# Schematic_SensorTapeMaster_v1.net
KiCad netlist of a schematic drawn in Altium Designer
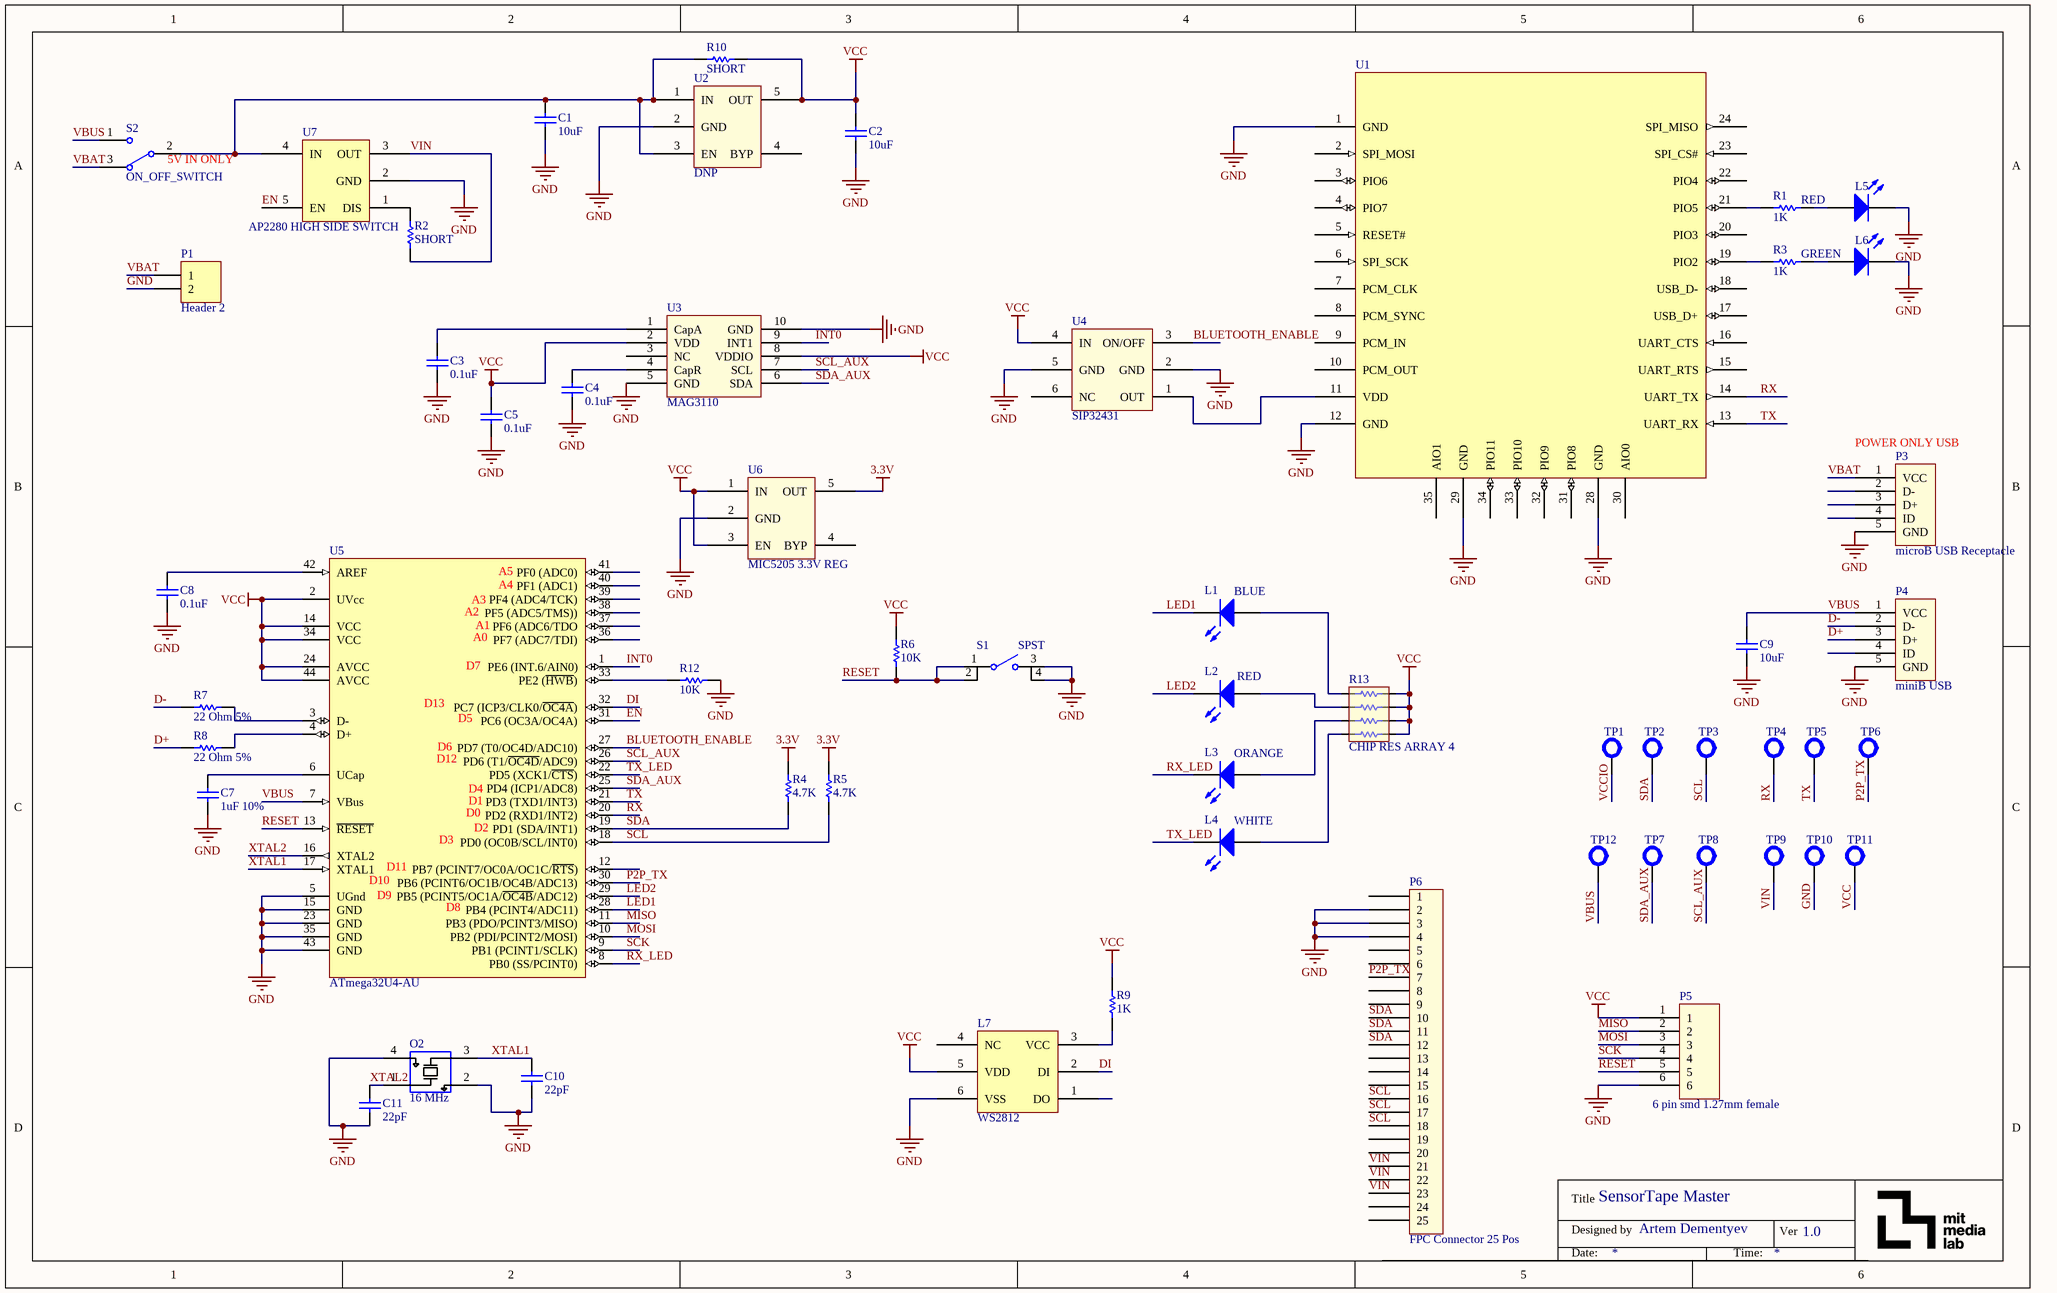
[diagram p0: Schematic_SensorTapeMaster_v1.SchDoc]

(export (version "E")
  (design (tool "Eeschema 10.0.6"))
  (components
    (comp (ref "C1")
      (value "10uF")
      (footprint "0603W")
      (description "SMD Cap 1206")
      (libsource (lib "Artem_Library") (part "Capacitor"))
    )
    (comp (ref "C2")
      (value "10uF")
      (footprint "0603W")
      (description "SMD Cap 1206")
      (libsource (lib "Artem_Library") (part "Capacitor"))
    )
    (comp (ref "C3")
      (value "0.1uF")
      (footprint "0603W")
      (description "SMD Cap 1206")
      (libsource (lib "Artem_Library") (part "Capacitor"))
    )
    (comp (ref "C4")
      (value "0.1uF")
      (footprint "0603W")
      (description "SMD Cap 1206")
      (libsource (lib "Artem_Library") (part "Capacitor"))
    )
    (comp (ref "C5")
      (value "0.1uF")
      (footprint "0603W")
      (description "SMD Cap 1206")
      (libsource (lib "Artem_Library") (part "Capacitor"))
    )
    (comp (ref "C7")
      (value "1uF 10%")
      (footprint "0603W")
      (description "SMD Cap 1206")
      (libsource (lib "Artem_Library") (part "Capacitor"))
    )
    (comp (ref "C8")
      (value "0.1uF")
      (footprint "0603W")
      (description "SMD Cap 1206")
      (libsource (lib "Artem_Library") (part "Capacitor"))
    )
    (comp (ref "C9")
      (value "10uF")
      (footprint "0603W")
      (description "SMD Cap 1206")
      (libsource (lib "Artem_Library") (part "Capacitor"))
    )
    (comp (ref "C10")
      (value "22pF")
      (footprint "0603W")
      (description "SMD Cap 1206")
      (libsource (lib "Artem_Library") (part "Capacitor"))
    )
    (comp (ref "C11")
      (value "22pF")
      (footprint "0603W")
      (description "SMD Cap 1206")
      (libsource (lib "Artem_Library") (part "Capacitor"))
    )
    (comp (ref "L1")
      (value "BLUE")
      (footprint "0603W")
      (description "LED SMD 1206/0603")
      (libsource (lib "Artem_Library") (part "LED"))
    )
    (comp (ref "L2")
      (value "RED")
      (footprint "0603W")
      (description "LED SMD 1206/0603")
      (libsource (lib "Artem_Library") (part "LED"))
    )
    (comp (ref "L3")
      (value "ORANGE")
      (footprint "0603W")
      (description "LED SMD 1206/0603")
      (libsource (lib "Artem_Library") (part "LED"))
    )
    (comp (ref "L4")
      (value "WHITE")
      (footprint "0603W")
      (description "LED SMD 1206/0603")
      (libsource (lib "Artem_Library") (part "LED"))
    )
    (comp (ref "L5")
      (value "LED")
      (footprint "0603W")
      (description "LED SMD 1206/0603")
      (fields (field (name "DIGIKEY PART NUMBER") "160-1447-1-ND"))
      (libsource (lib "Artem_Library") (part "LED"))
    )
    (comp (ref "L6")
      (value "LED")
      (footprint "0603W")
      (description "LED SMD 1206/0603")
      (fields (field (name "DIGIKEY PART NUMBER") "160-1446-1-ND"))
      (libsource (lib "Artem_Library") (part "LED"))
    )
    (comp (ref "L7") (value "WS2812") (footprint "WS2812") (libsource (lib "Artem_Library") (part "WS2812")))
    (comp (ref "O2")
      (value "16 MHz")
      (footprint "CRYSTAL_SMD")
      (description "Surface mount crystal")
      (libsource (lib "Artem_Library") (part "Crystal_SMD"))
    )
    (comp (ref "P1")
      (value "Header 2")
      (footprint "HDR1X2")
      (description "Header, 2-Pin")
      (fields (field (name "PUBLISHER") "Altium Limited"))
      (libsource (lib "Miscellaneous Connectors") (part "Header 2"))
    )
    (comp (ref "P3")
      (value "microB USB Receptacle")
      (footprint "MicroB USB Standarad SMT")
      (fields (field (name "MANUFACTURER") "ZX62-B-5PA(11)"))
      (libsource (lib "Artem_Library") (part "microB USB Receptacle"))
    )
    (comp (ref "P4")
      (value "miniB USB")
      (footprint "UX60SC-MB-5ST")
      (libsource (lib "Artem_Library") (part "miniB USB"))
    )
    (comp (ref "P5")
      (value "6 pin smd 1.27mm female")
      (footprint "6pos 1.27mm")
      (libsource (lib "Artem_Library") (part "6 pin smd 1.27mm female"))
    )
    (comp (ref "P6")
      (value "FPC Connector 25 Pos")
      (footprint "FPC 25 POS")
      (fields (field (name "DIGIKEY PART NUMBER") "A101410CT-ND"))
      (libsource (lib "Artem_Library") (part "FPC Connector 25 Pos"))
    )
    (comp (ref "R1") (value "1K") (footprint "0603W") (libsource (lib "Artem_Library") (part "Resistor")))
    (comp (ref "R2") (value "SHORT") (footprint "0603W") (libsource (lib "Artem_Library") (part "Resistor")))
    (comp (ref "R3") (value "1K") (footprint "0603W") (libsource (lib "Artem_Library") (part "Resistor")))
    (comp (ref "R4") (value "4.7K") (footprint "0603W") (libsource (lib "Artem_Library") (part "Resistor")))
    (comp (ref "R5") (value "4.7K") (footprint "0603W") (libsource (lib "Artem_Library") (part "Resistor")))
    (comp (ref "R6") (value "10K") (footprint "0603W") (libsource (lib "Artem_Library") (part "Resistor")))
    (comp (ref "R7")
      (value "22 Ohm 5%")
      (footprint "0603W")
      (libsource (lib "Artem_Library") (part "Resistor"))
    )
    (comp (ref "R8")
      (value "22 Ohm 5%")
      (footprint "0603W")
      (libsource (lib "Artem_Library") (part "Resistor"))
    )
    (comp (ref "R9") (value "1K") (footprint "0603W") (libsource (lib "Artem_Library") (part "Resistor")))
    (comp (ref "R10") (value "SHORT") (footprint "0603W") (libsource (lib "Artem_Library") (part "Resistor")))
    (comp (ref "R12") (value "10K") (footprint "0603W") (libsource (lib "Artem_Library") (part "Resistor")))
    (comp (ref "R13")
      (value "CHIP RES ARRAY 4")
      (footprint "RES ARRAY 4 1206")
      (libsource (lib "Artem_Library") (part "CHIP RES ARRAY 4"))
    )
    (comp (ref "S1")
      (value "SPST")
      (footprint "EVQQ2 Switch")
      (description "THD Button Switch")
      (libsource (lib "Artem_Library") (part "SPST"))
    )
    (comp (ref "S2")
      (value "ON_OFF_SWITCH")
      (footprint "SS321 Switch")
      (description "SPDT SMD Side Switch")
      (libsource (lib "Artem_Library") (part "ON_OFF_SWITCH"))
    )
    (comp (ref "TP1")
      (value "Test point small")
      (footprint "Test point small")
      (libsource (lib "Artem_Library") (part "Test point small"))
    )
    (comp (ref "TP2")
      (value "Test point small")
      (footprint "Test point small")
      (libsource (lib "Artem_Library") (part "Test point small"))
    )
    (comp (ref "TP3")
      (value "Test point small")
      (footprint "Test point small")
      (libsource (lib "Artem_Library") (part "Test point small"))
    )
    (comp (ref "TP4")
      (value "Test point small")
      (footprint "Test point small")
      (libsource (lib "Artem_Library") (part "Test point small"))
    )
    (comp (ref "TP5")
      (value "Test point small")
      (footprint "Test point small")
      (libsource (lib "Artem_Library") (part "Test point small"))
    )
    (comp (ref "TP6")
      (value "Test point small")
      (footprint "Test point small")
      (libsource (lib "Artem_Library") (part "Test point small"))
    )
    (comp (ref "TP7")
      (value "Test point small")
      (footprint "Test point small")
      (libsource (lib "Artem_Library") (part "Test point small"))
    )
    (comp (ref "TP8")
      (value "Test point small")
      (footprint "Test point small")
      (libsource (lib "Artem_Library") (part "Test point small"))
    )
    (comp (ref "TP9")
      (value "Test point small")
      (footprint "Test point small")
      (libsource (lib "Artem_Library") (part "Test point small"))
    )
    (comp (ref "TP10")
      (value "Test point small")
      (footprint "Test point small")
      (libsource (lib "Artem_Library") (part "Test point small"))
    )
    (comp (ref "TP11")
      (value "Test point small")
      (footprint "Test point small")
      (libsource (lib "Artem_Library") (part "Test point small"))
    )
    (comp (ref "TP12")
      (value "Test point small")
      (footprint "Test point small")
      (libsource (lib "Artem_Library") (part "Test point small"))
    )
    (comp (ref "U1")
      (value "~")
      (footprint "RN-42 LAND")
      (description "Bluetooth serial modem")
      (fields (field (name "DIGIKEY PART NUMBER") "740-1038-ND"))
      (libsource (lib "Artem_Library") (part "RN42"))
    )
    (comp (ref "U2")
      (value "DNP")
      (footprint "SOT-23-5")
      (description "5V LDO SMD")
      (libsource (lib "Artem_Library") (part "MIC5205_VOLTAGE_REG"))
    )
    (comp (ref "U3")
      (value "MAG3110")
      (footprint "10-VFDFN")
      (libsource (lib "Artem_Library") (part "MAG3110"))
    )
    (comp (ref "U4")
      (value "SIP32431")
      (footprint "SOT363")
      (description "High side switch")
      (fields (field (name "DIGIKEY PART NUMBER") "SIP32431DR3-T1GE3CT-ND"))
      (libsource (lib "Artem_Library") (part "SIP32431"))
    )
    (comp (ref "U5")
      (value "ATmega32U4-AU")
      (footprint "44ML_N")
      (fields (field (name "PUBLISHER") "Altium Limited"))
      (libsource (lib "Atmel Microcontroller 8-Bit megaAVR") (part "ATmega32U4-AU"))
    )
    (comp (ref "U6")
      (value "MIC5205 3.3V REG")
      (footprint "SOT-23-5")
      (description "5V LDO SMD")
      (libsource (lib "Artem_Library") (part "MIC5205_VOLTAGE_REG"))
    )
    (comp (ref "U7")
      (value "AP2280 HIGH SIDE SWITCH")
      (footprint "SOT25")
      (description "2A High side switch")
      (libsource (lib "Artem_Library") (part "AP2280 HIGH SIDE SWITCH"))
    )
  )
  (nets
    (net (code "1") (name "/BLUETOOTH_ENABLE") (class "Default")
      (node (ref "U4") (pin "3") (pinfunction "ON/OFF_3") (pintype "passive"))
      (node (ref "U5") (pin "27") (pinfunction "PD7_(T0/OC4D/ADC10)_27") (pintype "bidirectional"))
    )
    (net (code "2") (name "/D+") (class "Default")
      (node (ref "P4") (pin "3") (pinfunction "D+_3") (pintype "passive"))
      (node (ref "R8") (pin "2") (pinfunction "2_2") (pintype "passive"))
    )
    (net (code "3") (name "/D-") (class "Default")
      (node (ref "P4") (pin "2") (pinfunction "D-_2") (pintype "passive"))
      (node (ref "R7") (pin "2") (pinfunction "2_2") (pintype "passive"))
    )
    (net (code "4") (name "/DI") (class "Default")
      (node (ref "L7") (pin "2") (pinfunction "DI_2") (pintype "passive"))
      (node (ref "U5") (pin "32") (pinfunction "PC7_(ICP3/CLK0/~{OC4A})_32") (pintype "bidirectional"))
    )
    (net (code "5") (name "/EN") (class "Default")
      (node (ref "U5") (pin "31") (pinfunction "PC6_(OC3A/OC4A)_31") (pintype "bidirectional"))
      (node (ref "U7") (pin "5") (pinfunction "EN_5") (pintype "passive"))
    )
    (net (code "6") (name "/INT0") (class "Default")
      (node (ref "U3") (pin "9") (pinfunction "INT1_9") (pintype "passive"))
      (node (ref "U5") (pin "1") (pinfunction "PE6_(INT.6/AIN0)_1") (pintype "bidirectional"))
    )
    (net (code "7") (name "/LED1") (class "Default")
      (node (ref "L1") (pin "2") (pinfunction "K_2") (pintype "passive"))
      (node (ref "U5") (pin "28") (pinfunction "PB4_(PCINT4/ADC11)_28") (pintype "bidirectional"))
    )
    (net (code "8") (name "/LED2") (class "Default")
      (node (ref "L2") (pin "2") (pinfunction "K_2") (pintype "passive"))
      (node (ref "U5") (pin "29") (pinfunction "PB5_(PCINT5/OC1A/~{OC4B}/ADC12)_29") (pintype "bidirectional"))
    )
    (net (code "9") (name "/MISO") (class "Default")
      (node (ref "P5") (pin "2") (pinfunction "2_2") (pintype "passive"))
      (node (ref "U5") (pin "11") (pinfunction "PB3_(PDO/PCINT3/MISO)_11") (pintype "bidirectional"))
    )
    (net (code "10") (name "/MOSI") (class "Default")
      (node (ref "P5") (pin "3") (pinfunction "3_3") (pintype "passive"))
      (node (ref "U5") (pin "10") (pinfunction "PB2_(PDI/PCINT2/MOSI)_10") (pintype "bidirectional"))
    )
    (net (code "11") (name "/P2P_TX") (class "Default")
      (node (ref "P6") (pin "7") (pinfunction "7_7") (pintype "passive"))
      (node (ref "TP6") (pin "0") (pinfunction "0_0") (pintype "passive"))
      (node (ref "U5") (pin "30") (pinfunction "PB6_(PCINT6/OC1B/OC4B/ADC13)_30") (pintype "bidirectional"))
    )
    (net (code "12") (name "/RESET") (class "Default")
      (node (ref "P5") (pin "5") (pinfunction "5_5") (pintype "passive"))
      (node (ref "R6") (pin "1") (pinfunction "1_1") (pintype "passive"))
      (node (ref "S1") (pin "1") (pinfunction "COMMON_1") (pintype "passive"))
      (node (ref "S1") (pin "2") (pinfunction "2_2") (pintype "passive"))
      (node (ref "U5") (pin "13") (pinfunction "~{RESET}_13") (pintype "input"))
    )
    (net (code "13") (name "/RX") (class "Default")
      (node (ref "TP4") (pin "0") (pinfunction "0_0") (pintype "passive"))
      (node (ref "U1") (pin "14") (pinfunction "UART_TX_14") (pintype "output"))
      (node (ref "U5") (pin "20") (pinfunction "PD2_(RXD1/INT2)_20") (pintype "bidirectional"))
    )
    (net (code "14") (name "/RX_LED") (class "Default")
      (node (ref "L3") (pin "2") (pinfunction "K_2") (pintype "passive"))
      (node (ref "U5") (pin "8") (pinfunction "PB0_(SS/PCINT0)_8") (pintype "bidirectional"))
    )
    (net (code "15") (name "/SCK") (class "Default")
      (node (ref "P5") (pin "4") (pinfunction "4_4") (pintype "passive"))
      (node (ref "U5") (pin "9") (pinfunction "PB1_(PCINT1/SCLK)_9") (pintype "bidirectional"))
    )
    (net (code "16") (name "/SCL") (class "Default")
      (node (ref "P6") (pin "16") (pinfunction "16_16") (pintype "passive"))
      (node (ref "P6") (pin "17") (pinfunction "17_17") (pintype "passive"))
      (node (ref "P6") (pin "18") (pinfunction "18_18") (pintype "passive"))
      (node (ref "R5") (pin "1") (pinfunction "1_1") (pintype "passive"))
      (node (ref "TP3") (pin "0") (pinfunction "0_0") (pintype "passive"))
      (node (ref "U5") (pin "18") (pinfunction "PD0_(OC0B/SCL/INT0)_18") (pintype "bidirectional"))
    )
    (net (code "17") (name "/SCL_AUX") (class "Default")
      (node (ref "TP8") (pin "0") (pinfunction "0_0") (pintype "passive"))
      (node (ref "U3") (pin "7") (pinfunction "SCL_7") (pintype "passive"))
      (node (ref "U5") (pin "26") (pinfunction "PD6_(T1/~{OC4D}/ADC9)_26") (pintype "bidirectional"))
    )
    (net (code "18") (name "/SDA") (class "Default")
      (node (ref "P6") (pin "10") (pinfunction "10_10") (pintype "passive"))
      (node (ref "P6") (pin "11") (pinfunction "11_11") (pintype "passive"))
      (node (ref "P6") (pin "12") (pinfunction "12_12") (pintype "passive"))
      (node (ref "R4") (pin "2") (pinfunction "2_2") (pintype "passive"))
      (node (ref "TP2") (pin "0") (pinfunction "0_0") (pintype "passive"))
      (node (ref "U5") (pin "19") (pinfunction "PD1_(SDA/INT1)_19") (pintype "bidirectional"))
    )
    (net (code "19") (name "/SDA_AUX") (class "Default")
      (node (ref "TP7") (pin "0") (pinfunction "0_0") (pintype "passive"))
      (node (ref "U3") (pin "6") (pinfunction "SDA_6") (pintype "passive"))
      (node (ref "U5") (pin "25") (pinfunction "PD4_(ICP1/ADC8)_25") (pintype "bidirectional"))
    )
    (net (code "20") (name "/TX") (class "Default")
      (node (ref "TP5") (pin "0") (pinfunction "0_0") (pintype "passive"))
      (node (ref "U1") (pin "13") (pinfunction "UART_RX_13") (pintype "input"))
      (node (ref "U5") (pin "21") (pinfunction "PD3_(TXD1/INT3)_21") (pintype "bidirectional"))
    )
    (net (code "21") (name "/TX_LED") (class "Default")
      (node (ref "L4") (pin "2") (pinfunction "K_2") (pintype "passive"))
      (node (ref "U5") (pin "22") (pinfunction "PD5_(XCK1/~{CTS})_22") (pintype "bidirectional"))
    )
    (net (code "22") (name "/VBAT") (class "Default")
      (node (ref "P1") (pin "1") (pinfunction "1_1") (pintype "passive"))
      (node (ref "P3") (pin "1") (pinfunction "VCC_1") (pintype "passive"))
      (node (ref "S2") (pin "3") (pinfunction "3_3") (pintype "passive"))
    )
    (net (code "23") (name "/VBUS") (class "Default")
      (node (ref "C9") (pin "1") (pinfunction "1_1") (pintype "passive"))
      (node (ref "P4") (pin "1") (pinfunction "VCC_1") (pintype "passive"))
      (node (ref "S2") (pin "1") (pinfunction "1_1") (pintype "passive"))
      (node (ref "TP12") (pin "0") (pinfunction "0_0") (pintype "passive"))
      (node (ref "U5") (pin "7") (pinfunction "VBus_7") (pintype "input"))
    )
    (net (code "24") (name "/VCCIO") (class "Default")
      (node (ref "TP1") (pin "0") (pinfunction "0_0") (pintype "passive"))
    )
    (net (code "25") (name "/VIN") (class "Default")
      (node (ref "P6") (pin "21") (pinfunction "21_21") (pintype "passive"))
      (node (ref "P6") (pin "22") (pinfunction "22_22") (pintype "passive"))
      (node (ref "P6") (pin "23") (pinfunction "23_23") (pintype "passive"))
      (node (ref "R2") (pin "1") (pinfunction "1_1") (pintype "passive"))
      (node (ref "TP9") (pin "0") (pinfunction "0_0") (pintype "passive"))
      (node (ref "U7") (pin "3") (pinfunction "OUT_3") (pintype "passive"))
    )
    (net (code "26") (name "/XTAL1") (class "Default")
      (node (ref "C10") (pin "1") (pinfunction "1_1") (pintype "passive"))
      (node (ref "O2") (pin "3") (pinfunction "XOUT_3") (pintype "passive"))
      (node (ref "U5") (pin "17") (pinfunction "XTAL1_17") (pintype "input"))
    )
    (net (code "27") (name "/XTAL2") (class "Default")
      (node (ref "C11") (pin "1") (pinfunction "1_1") (pintype "passive"))
      (node (ref "O2") (pin "1") (pinfunction "XIN_1") (pintype "passive"))
      (node (ref "U5") (pin "16") (pinfunction "XTAL2_16") (pintype "output"))
    )
    (net (code "28") (name "3.3V") (class "Default")
      (node (ref "R4") (pin "1") (pinfunction "1_1") (pintype "passive"))
      (node (ref "R5") (pin "2") (pinfunction "2_2") (pintype "passive"))
      (node (ref "U6") (pin "5") (pinfunction "OUT_5") (pintype "passive"))
    )
    (net (code "29") (name "GND") (class "Default")
      (node (ref "C1") (pin "1") (pinfunction "1_1") (pintype "passive"))
      (node (ref "C10") (pin "2") (pinfunction "2_2") (pintype "passive"))
      (node (ref "C11") (pin "2") (pinfunction "2_2") (pintype "passive"))
      (node (ref "C2") (pin "1") (pinfunction "1_1") (pintype "passive"))
      (node (ref "C3") (pin "1") (pinfunction "1_1") (pintype "passive"))
      (node (ref "C4") (pin "1") (pinfunction "1_1") (pintype "passive"))
      (node (ref "C5") (pin "1") (pinfunction "1_1") (pintype "passive"))
      (node (ref "C7") (pin "2") (pinfunction "2_2") (pintype "passive"))
      (node (ref "C8") (pin "2") (pinfunction "2_2") (pintype "passive"))
      (node (ref "C9") (pin "2") (pinfunction "2_2") (pintype "passive"))
      (node (ref "L5") (pin "2") (pinfunction "K_2") (pintype "passive"))
      (node (ref "L6") (pin "2") (pinfunction "K_2") (pintype "passive"))
      (node (ref "L7") (pin "6") (pinfunction "VSS_6") (pintype "passive"))
      (node (ref "O2") (pin "2") (pinfunction "Gnd_2") (pintype "passive"))
      (node (ref "O2") (pin "4") (pinfunction "Gnd_4") (pintype "passive"))
      (node (ref "P1") (pin "2") (pinfunction "2_2") (pintype "passive"))
      (node (ref "P3") (pin "5") (pinfunction "GND_5") (pintype "passive"))
      (node (ref "P4") (pin "5") (pinfunction "GND_5") (pintype "passive"))
      (node (ref "P5") (pin "6") (pinfunction "6_6") (pintype "passive"))
      (node (ref "P6") (pin "2") (pinfunction "2_2") (pintype "passive"))
      (node (ref "P6") (pin "3") (pinfunction "3_3") (pintype "passive"))
      (node (ref "P6") (pin "4") (pinfunction "4_4") (pintype "passive"))
      (node (ref "R12") (pin "1") (pinfunction "1_1") (pintype "passive"))
      (node (ref "S1") (pin "3") (pinfunction "3_3") (pintype "passive"))
      (node (ref "S1") (pin "4") (pinfunction "4_4") (pintype "passive"))
      (node (ref "TP10") (pin "0") (pinfunction "0_0") (pintype "passive"))
      (node (ref "U1") (pin "1") (pinfunction "GND_1") (pintype "power_in"))
      (node (ref "U1") (pin "12") (pinfunction "GND_12") (pintype "power_in"))
      (node (ref "U1") (pin "28") (pinfunction "GND_28") (pintype "power_in"))
      (node (ref "U1") (pin "29") (pinfunction "GND_29") (pintype "power_in"))
      (node (ref "U2") (pin "2") (pinfunction "GND_2") (pintype "passive"))
      (node (ref "U3") (pin "10") (pinfunction "GND_10") (pintype "passive"))
      (node (ref "U3") (pin "5") (pinfunction "GND_5") (pintype "passive"))
      (node (ref "U4") (pin "2") (pinfunction "GND_2") (pintype "passive"))
      (node (ref "U4") (pin "5") (pinfunction "GND_5") (pintype "passive"))
      (node (ref "U5") (pin "15") (pinfunction "GND_15") (pintype "power_in"))
      (node (ref "U5") (pin "23") (pinfunction "GND_23") (pintype "power_in"))
      (node (ref "U5") (pin "35") (pinfunction "GND_35") (pintype "power_in"))
      (node (ref "U5") (pin "43") (pinfunction "GND_43") (pintype "power_in"))
      (node (ref "U5") (pin "5") (pinfunction "UGnd_5") (pintype "power_in"))
      (node (ref "U6") (pin "2") (pinfunction "GND_2") (pintype "passive"))
      (node (ref "U7") (pin "2") (pinfunction "GND_2") (pintype "passive"))
    )
    (net (code "30") (name "Net-(L1-A)") (class "Default")
      (node (ref "L1") (pin "1") (pinfunction "A_1") (pintype "passive"))
      (node (ref "R13") (pin "1") (pinfunction "1_1") (pintype "passive"))
    )
    (net (code "31") (name "Net-(L2-A)") (class "Default")
      (node (ref "L2") (pin "1") (pinfunction "A_1") (pintype "passive"))
      (node (ref "R13") (pin "2") (pinfunction "2_2") (pintype "passive"))
    )
    (net (code "32") (name "Net-(L3-A)") (class "Default")
      (node (ref "L3") (pin "1") (pinfunction "A_1") (pintype "passive"))
      (node (ref "R13") (pin "3") (pinfunction "3_3") (pintype "passive"))
    )
    (net (code "33") (name "Net-(L4-A)") (class "Default")
      (node (ref "L4") (pin "1") (pinfunction "A_1") (pintype "passive"))
      (node (ref "R13") (pin "4") (pinfunction "4_4") (pintype "passive"))
    )
    (net (code "34") (name "Net-(L5-A)") (class "Default")
      (node (ref "L5") (pin "1") (pinfunction "A_1") (pintype "passive"))
      (node (ref "R1") (pin "1") (pinfunction "1_1") (pintype "passive"))
    )
    (net (code "35") (name "Net-(L6-A)") (class "Default")
      (node (ref "L6") (pin "1") (pinfunction "A_1") (pintype "passive"))
      (node (ref "R3") (pin "1") (pinfunction "1_1") (pintype "passive"))
    )
    (net (code "36") (name "Net-(L7-VCC)") (class "Default")
      (node (ref "L7") (pin "3") (pinfunction "VCC_3") (pintype "passive"))
      (node (ref "R9") (pin "1") (pinfunction "1_1") (pintype "passive"))
    )
    (net (code "37") (name "Net-(U1-PIO2)") (class "Default")
      (node (ref "R3") (pin "2") (pinfunction "2_2") (pintype "passive"))
      (node (ref "U1") (pin "19") (pinfunction "PIO2_19") (pintype "bidirectional"))
    )
    (net (code "38") (name "Net-(U1-PIO5)") (class "Default")
      (node (ref "R1") (pin "2") (pinfunction "2_2") (pintype "passive"))
      (node (ref "U1") (pin "21") (pinfunction "PIO5_21") (pintype "bidirectional"))
    )
    (net (code "39") (name "Net-(U1-VDD)") (class "Default")
      (node (ref "U1") (pin "11") (pinfunction "VDD_11") (pintype "power_in"))
      (node (ref "U4") (pin "1") (pinfunction "OUT_1") (pintype "passive"))
    )
    (net (code "40") (name "Net-(U2-EN)") (class "Default")
      (node (ref "C1") (pin "2") (pinfunction "2_2") (pintype "passive"))
      (node (ref "R10") (pin "2") (pinfunction "2_2") (pintype "passive"))
      (node (ref "S2") (pin "2") (pinfunction "2_2") (pintype "passive"))
      (node (ref "U2") (pin "1") (pinfunction "IN_1") (pintype "passive"))
      (node (ref "U2") (pin "3") (pinfunction "EN_3") (pintype "passive"))
      (node (ref "U7") (pin "4") (pinfunction "IN_4") (pintype "passive"))
    )
    (net (code "41") (name "Net-(U3-CapA)") (class "Default")
      (node (ref "C3") (pin "2") (pinfunction "2_2") (pintype "passive"))
      (node (ref "U3") (pin "1") (pinfunction "CapA_1") (pintype "passive"))
    )
    (net (code "42") (name "Net-(U3-CapR)") (class "Default")
      (node (ref "C4") (pin "2") (pinfunction "2_2") (pintype "passive"))
      (node (ref "U3") (pin "4") (pinfunction "CapR_4") (pintype "passive"))
    )
    (net (code "43") (name "Net-(U5-AREF)") (class "Default")
      (node (ref "C8") (pin "1") (pinfunction "1_1") (pintype "passive"))
      (node (ref "U5") (pin "42") (pinfunction "AREF_42") (pintype "input"))
    )
    (net (code "44") (name "Net-(U5-D+)") (class "Default")
      (node (ref "R8") (pin "1") (pinfunction "1_1") (pintype "passive"))
      (node (ref "U5") (pin "4") (pinfunction "D+_4") (pintype "bidirectional"))
    )
    (net (code "45") (name "Net-(U5-D-)") (class "Default")
      (node (ref "R7") (pin "1") (pinfunction "1_1") (pintype "passive"))
      (node (ref "U5") (pin "3") (pinfunction "D-_3") (pintype "bidirectional"))
    )
    (net (code "46") (name "Net-(U5-PE2_(~{HWB}))") (class "Default")
      (node (ref "R12") (pin "2") (pinfunction "2_2") (pintype "passive"))
      (node (ref "U5") (pin "33") (pinfunction "PE2_(~{HWB})_33") (pintype "bidirectional"))
    )
    (net (code "47") (name "Net-(U5-UCap)") (class "Default")
      (node (ref "C7") (pin "1") (pinfunction "1_1") (pintype "passive"))
      (node (ref "U5") (pin "6") (pinfunction "UCap_6") (pintype "passive"))
    )
    (net (code "48") (name "Net-(U7-DIS)") (class "Default")
      (node (ref "R2") (pin "2") (pinfunction "2_2") (pintype "passive"))
      (node (ref "U7") (pin "1") (pinfunction "DIS_1") (pintype "passive"))
    )
    (net (code "49") (name "VCC") (class "Default")
      (node (ref "C2") (pin "2") (pinfunction "2_2") (pintype "passive"))
      (node (ref "C5") (pin "2") (pinfunction "2_2") (pintype "passive"))
      (node (ref "L7") (pin "5") (pinfunction "VDD_5") (pintype "passive"))
      (node (ref "P5") (pin "1") (pinfunction "1_1") (pintype "passive"))
      (node (ref "R10") (pin "1") (pinfunction "1_1") (pintype "passive"))
      (node (ref "R13") (pin "5") (pinfunction "5_5") (pintype "passive"))
      (node (ref "R13") (pin "6") (pinfunction "6_6") (pintype "passive"))
      (node (ref "R13") (pin "7") (pinfunction "7_7") (pintype "passive"))
      (node (ref "R13") (pin "8") (pinfunction "8_8") (pintype "passive"))
      (node (ref "R6") (pin "2") (pinfunction "2_2") (pintype "passive"))
      (node (ref "R9") (pin "2") (pinfunction "2_2") (pintype "passive"))
      (node (ref "TP11") (pin "0") (pinfunction "0_0") (pintype "passive"))
      (node (ref "U2") (pin "5") (pinfunction "OUT_5") (pintype "passive"))
      (node (ref "U3") (pin "2") (pinfunction "VDD_2") (pintype "passive"))
      (node (ref "U3") (pin "8") (pinfunction "VDDIO_8") (pintype "passive"))
      (node (ref "U4") (pin "4") (pinfunction "IN_4") (pintype "passive"))
      (node (ref "U5") (pin "14") (pinfunction "VCC_14") (pintype "power_in"))
      (node (ref "U5") (pin "2") (pinfunction "UVcc_2") (pintype "power_in"))
      (node (ref "U5") (pin "24") (pinfunction "AVCC_24") (pintype "power_in"))
      (node (ref "U5") (pin "34") (pinfunction "VCC_34") (pintype "power_in"))
      (node (ref "U5") (pin "44") (pinfunction "AVCC_44") (pintype "power_in"))
      (node (ref "U6") (pin "1") (pinfunction "IN_1") (pintype "passive"))
      (node (ref "U6") (pin "3") (pinfunction "EN_3") (pintype "passive"))
    )
    (net (code "50") (name "unconnected-(L7-DO-Pad1)") (class "Default")
      (node (ref "L7") (pin "1") (pinfunction "DO_1") (pintype "passive"))
    )
    (net (code "51") (name "unconnected-(L7-NC-Pad4)") (class "Default")
      (node (ref "L7") (pin "4") (pinfunction "NC_4") (pintype "passive"))
    )
    (net (code "52") (name "unconnected-(P3-D+-Pad3)") (class "Default")
      (node (ref "P3") (pin "3") (pinfunction "D+_3") (pintype "passive"))
    )
    (net (code "53") (name "unconnected-(P3-D--Pad2)") (class "Default")
      (node (ref "P3") (pin "2") (pinfunction "D-_2") (pintype "passive"))
    )
    (net (code "54") (name "unconnected-(P3-ID-Pad4)") (class "Default")
      (node (ref "P3") (pin "4") (pinfunction "ID_4") (pintype "passive"))
    )
    (net (code "55") (name "unconnected-(P4-ID-Pad4)") (class "Default")
      (node (ref "P4") (pin "4") (pinfunction "ID_4") (pintype "passive"))
    )
    (net (code "56") (name "unconnected-(P6-Pad1)") (class "Default")
      (node (ref "P6") (pin "1") (pinfunction "1_1") (pintype "passive"))
    )
    (net (code "57") (name "unconnected-(P6-Pad5)") (class "Default")
      (node (ref "P6") (pin "5") (pinfunction "5_5") (pintype "passive"))
    )
    (net (code "58") (name "unconnected-(P6-Pad6)") (class "Default")
      (node (ref "P6") (pin "6") (pinfunction "6_6") (pintype "passive"))
    )
    (net (code "59") (name "unconnected-(P6-Pad8)") (class "Default")
      (node (ref "P6") (pin "8") (pinfunction "8_8") (pintype "passive"))
    )
    (net (code "60") (name "unconnected-(P6-Pad9)") (class "Default")
      (node (ref "P6") (pin "9") (pinfunction "9_9") (pintype "passive"))
    )
    (net (code "61") (name "unconnected-(P6-Pad13)") (class "Default")
      (node (ref "P6") (pin "13") (pinfunction "13_13") (pintype "passive"))
    )
    (net (code "62") (name "unconnected-(P6-Pad14)") (class "Default")
      (node (ref "P6") (pin "14") (pinfunction "14_14") (pintype "passive"))
    )
    (net (code "63") (name "unconnected-(P6-Pad15)") (class "Default")
      (node (ref "P6") (pin "15") (pinfunction "15_15") (pintype "passive"))
    )
    (net (code "64") (name "unconnected-(P6-Pad19)") (class "Default")
      (node (ref "P6") (pin "19") (pinfunction "19_19") (pintype "passive"))
    )
    (net (code "65") (name "unconnected-(P6-Pad20)") (class "Default")
      (node (ref "P6") (pin "20") (pinfunction "20_20") (pintype "passive"))
    )
    (net (code "66") (name "unconnected-(P6-Pad24)") (class "Default")
      (node (ref "P6") (pin "24") (pinfunction "24_24") (pintype "passive"))
    )
    (net (code "67") (name "unconnected-(P6-Pad25)") (class "Default")
      (node (ref "P6") (pin "25") (pinfunction "25_25") (pintype "passive"))
    )
    (net (code "68") (name "unconnected-(U1-AIO0-Pad30)") (class "Default")
      (node (ref "U1") (pin "30") (pinfunction "AIO0_30") (pintype "passive"))
    )
    (net (code "69") (name "unconnected-(U1-AIO1-Pad35)") (class "Default")
      (node (ref "U1") (pin "35") (pinfunction "AIO1_35") (pintype "passive"))
    )
    (net (code "70") (name "unconnected-(U1-PCM_CLK-Pad7)") (class "Default")
      (node (ref "U1") (pin "7") (pinfunction "PCM_CLK_7") (pintype "passive"))
    )
    (net (code "71") (name "unconnected-(U1-PCM_IN-Pad9)") (class "Default")
      (node (ref "U1") (pin "9") (pinfunction "PCM_IN_9") (pintype "passive"))
    )
    (net (code "72") (name "unconnected-(U1-PCM_OUT-Pad10)") (class "Default")
      (node (ref "U1") (pin "10") (pinfunction "PCM_OUT_10") (pintype "passive"))
    )
    (net (code "73") (name "unconnected-(U1-PCM_SYNC-Pad8)") (class "Default")
      (node (ref "U1") (pin "8") (pinfunction "PCM_SYNC_8") (pintype "passive"))
    )
    (net (code "74") (name "unconnected-(U1-PIO3-Pad20)") (class "Default")
      (node (ref "U1") (pin "20") (pinfunction "PIO3_20") (pintype "bidirectional"))
    )
    (net (code "75") (name "unconnected-(U1-PIO4-Pad22)") (class "Default")
      (node (ref "U1") (pin "22") (pinfunction "PIO4_22") (pintype "bidirectional"))
    )
    (net (code "76") (name "unconnected-(U1-PIO6-Pad3)") (class "Default")
      (node (ref "U1") (pin "3") (pinfunction "PIO6_3") (pintype "bidirectional"))
    )
    (net (code "77") (name "unconnected-(U1-PIO7-Pad4)") (class "Default")
      (node (ref "U1") (pin "4") (pinfunction "PIO7_4") (pintype "bidirectional"))
    )
    (net (code "78") (name "unconnected-(U1-PIO8-Pad31)") (class "Default")
      (node (ref "U1") (pin "31") (pinfunction "PIO8_31") (pintype "bidirectional"))
    )
    (net (code "79") (name "unconnected-(U1-PIO9-Pad32)") (class "Default")
      (node (ref "U1") (pin "32") (pinfunction "PIO9_32") (pintype "bidirectional"))
    )
    (net (code "80") (name "unconnected-(U1-PIO10-Pad33)") (class "Default")
      (node (ref "U1") (pin "33") (pinfunction "PIO10_33") (pintype "bidirectional"))
    )
    (net (code "81") (name "unconnected-(U1-PIO11-Pad34)") (class "Default")
      (node (ref "U1") (pin "34") (pinfunction "PIO11_34") (pintype "bidirectional"))
    )
    (net (code "82") (name "unconnected-(U1-RESET#-Pad5)") (class "Default")
      (node (ref "U1") (pin "5") (pinfunction "RESET#_5") (pintype "input"))
    )
    (net (code "83") (name "unconnected-(U1-SPI_CS#-Pad23)") (class "Default")
      (node (ref "U1") (pin "23") (pinfunction "SPI_CS#_23") (pintype "input"))
    )
    (net (code "84") (name "unconnected-(U1-SPI_MISO-Pad24)") (class "Default")
      (node (ref "U1") (pin "24") (pinfunction "SPI_MISO_24") (pintype "output"))
    )
    (net (code "85") (name "unconnected-(U1-SPI_MOSI-Pad2)") (class "Default")
      (node (ref "U1") (pin "2") (pinfunction "SPI_MOSI_2") (pintype "input"))
    )
    (net (code "86") (name "unconnected-(U1-SPI_SCK-Pad6)") (class "Default")
      (node (ref "U1") (pin "6") (pinfunction "SPI_SCK_6") (pintype "input"))
    )
    (net (code "87") (name "unconnected-(U1-UART_CTS-Pad16)") (class "Default")
      (node (ref "U1") (pin "16") (pinfunction "UART_CTS_16") (pintype "input"))
    )
    (net (code "88") (name "unconnected-(U1-UART_RTS-Pad15)") (class "Default")
      (node (ref "U1") (pin "15") (pinfunction "UART_RTS_15") (pintype "output"))
    )
    (net (code "89") (name "unconnected-(U1-USB_D+-Pad17)") (class "Default")
      (node (ref "U1") (pin "17") (pinfunction "USB_D+_17") (pintype "bidirectional"))
    )
    (net (code "90") (name "unconnected-(U1-USB_D--Pad18)") (class "Default")
      (node (ref "U1") (pin "18") (pinfunction "USB_D-_18") (pintype "bidirectional"))
    )
    (net (code "91") (name "unconnected-(U2-BYP-Pad4)") (class "Default")
      (node (ref "U2") (pin "4") (pinfunction "BYP_4") (pintype "passive"))
    )
    (net (code "92") (name "unconnected-(U3-NC-Pad3)") (class "Default")
      (node (ref "U3") (pin "3") (pinfunction "NC_3") (pintype "passive"))
    )
    (net (code "93") (name "unconnected-(U4-NC-Pad6)") (class "Default")
      (node (ref "U4") (pin "6") (pinfunction "NC_6") (pintype "passive"))
    )
    (net (code "94") (name "unconnected-(U5-PB7_(PCINT7{slash}OC0A{slash}OC1C{slash}~{RTS})-Pad12)") (class "Default")
      (node (ref "U5") (pin "12") (pinfunction "PB7_(PCINT7/OC0A/OC1C/~{RTS})_12") (pintype "bidirectional"))
    )
    (net (code "95") (name "unconnected-(U5-PF0_(ADC0)-Pad41)") (class "Default")
      (node (ref "U5") (pin "41") (pinfunction "PF0_(ADC0)_41") (pintype "bidirectional"))
    )
    (net (code "96") (name "unconnected-(U5-PF1_(ADC1)-Pad40)") (class "Default")
      (node (ref "U5") (pin "40") (pinfunction "PF1_(ADC1)_40") (pintype "bidirectional"))
    )
    (net (code "97") (name "unconnected-(U5-PF4_(ADC4{slash}TCK)-Pad39)") (class "Default")
      (node (ref "U5") (pin "39") (pinfunction "PF4_(ADC4/TCK)_39") (pintype "bidirectional"))
    )
    (net (code "98") (name "unconnected-(U5-PF5_(ADC5{slash}TMS))-Pad38)") (class "Default")
      (node (ref "U5") (pin "38") (pinfunction "PF5_(ADC5/TMS))_38") (pintype "bidirectional"))
    )
    (net (code "99") (name "unconnected-(U5-PF6_(ADC6{slash}TDO-Pad37)") (class "Default")
      (node (ref "U5") (pin "37") (pinfunction "PF6_(ADC6/TDO_37") (pintype "bidirectional"))
    )
    (net (code "100") (name "unconnected-(U5-PF7_(ADC7{slash}TDI)-Pad36)") (class "Default")
      (node (ref "U5") (pin "36") (pinfunction "PF7_(ADC7/TDI)_36") (pintype "bidirectional"))
    )
    (net (code "101") (name "unconnected-(U6-BYP-Pad4)") (class "Default")
      (node (ref "U6") (pin "4") (pinfunction "BYP_4") (pintype "passive"))
    )
  )
)
